# USB-C.net
KiCad netlist of a schematic drawn in Altium Designer
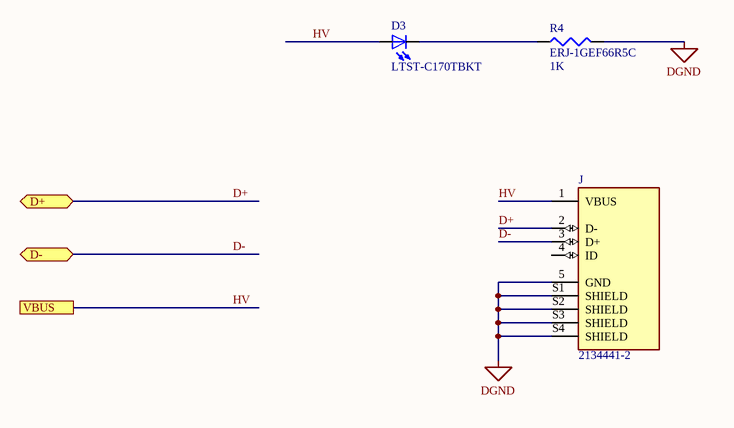
[diagram p0: USB-C.SchDoc]

(export (version "E")
  (design (tool "Eeschema 10.0.6"))
  (components
    (comp (ref "D3")
      (value "LTST-C170TBKT")
      (footprint "DIOC200X125X110")
      (description "Blue 470nm LED Indication - Discrete 3.3V 0805 _2012 Metric_")
      (fields (field (name "MF") "Lite-On Inc.") (field (name "DIGI-KEY_PART_NUMBER") "160-1579-1-ND"))
      (libsource (lib "Led") (part "LTST-C170TBKT"))
    )
    (comp (ref "J")
      (value "2134441-2")
      (footprint "TE_2134441-2")
      (description "Conn Micro USB RCP 5 POS 0.65mm Solder RA SMD 5 Terminal 1 Port T/R")
      (fields (field (name "MF") "TE Connectivity") (field (name "DIGI-KEY_PART_NUMBER") "A118104CT-ND"))
      (libsource (lib "SnapEDAsch") (part "2134441-2"))
    )
    (comp (ref "R4")
      (value "ERJ-1GEF66R5C")
      (footprint "J1-0603")
      (description "Resistor")
      (fields (field (name "ALTIUM_VALUE") "1K") (field (name "PUBLISHER") "Altium Limited"))
      (libsource (lib "Miscellaneous Devices") (part "Res3"))
    )
  )
  (nets
    (net (code "1") (name "/D+") (class "Default")
      (node (ref "J") (pin "2") (pinfunction "D-_2") (pintype "bidirectional"))
    )
    (net (code "2") (name "/D-") (class "Default")
      (node (ref "J") (pin "3") (pinfunction "D+_3") (pintype "bidirectional"))
    )
    (net (code "3") (name "/HV") (class "Default")
      (node (ref "D3") (pin "POS") (pinfunction "POS_POS") (pintype "passive"))
      (node (ref "J") (pin "1") (pinfunction "VBUS_1") (pintype "power_in"))
    )
    (net (code "4") (name "DGND") (class "Default")
      (node (ref "J") (pin "5") (pinfunction "GND_5") (pintype "power_in"))
      (node (ref "J") (pin "S1") (pinfunction "SHIELD_S1") (pintype "power_in"))
      (node (ref "J") (pin "S2") (pinfunction "SHIELD_S2") (pintype "power_in"))
      (node (ref "J") (pin "S3") (pinfunction "SHIELD_S3") (pintype "power_in"))
      (node (ref "J") (pin "S4") (pinfunction "SHIELD_S4") (pintype "power_in"))
      (node (ref "R4") (pin "2") (pinfunction "2_2") (pintype "passive"))
    )
    (net (code "5") (name "Net-(D3-PadNEG)") (class "Default")
      (node (ref "D3") (pin "NEG") (pinfunction "NEG_NEG") (pintype "passive"))
      (node (ref "R4") (pin "1") (pinfunction "1_1") (pintype "passive"))
    )
    (net (code "6") (name "unconnected-(J-ID-Pad4)") (class "Default")
      (node (ref "J") (pin "4") (pinfunction "ID_4") (pintype "bidirectional"))
    )
  )
)
